# ep2c5_02.net
KiCad netlist of a schematic drawn in EAGLE
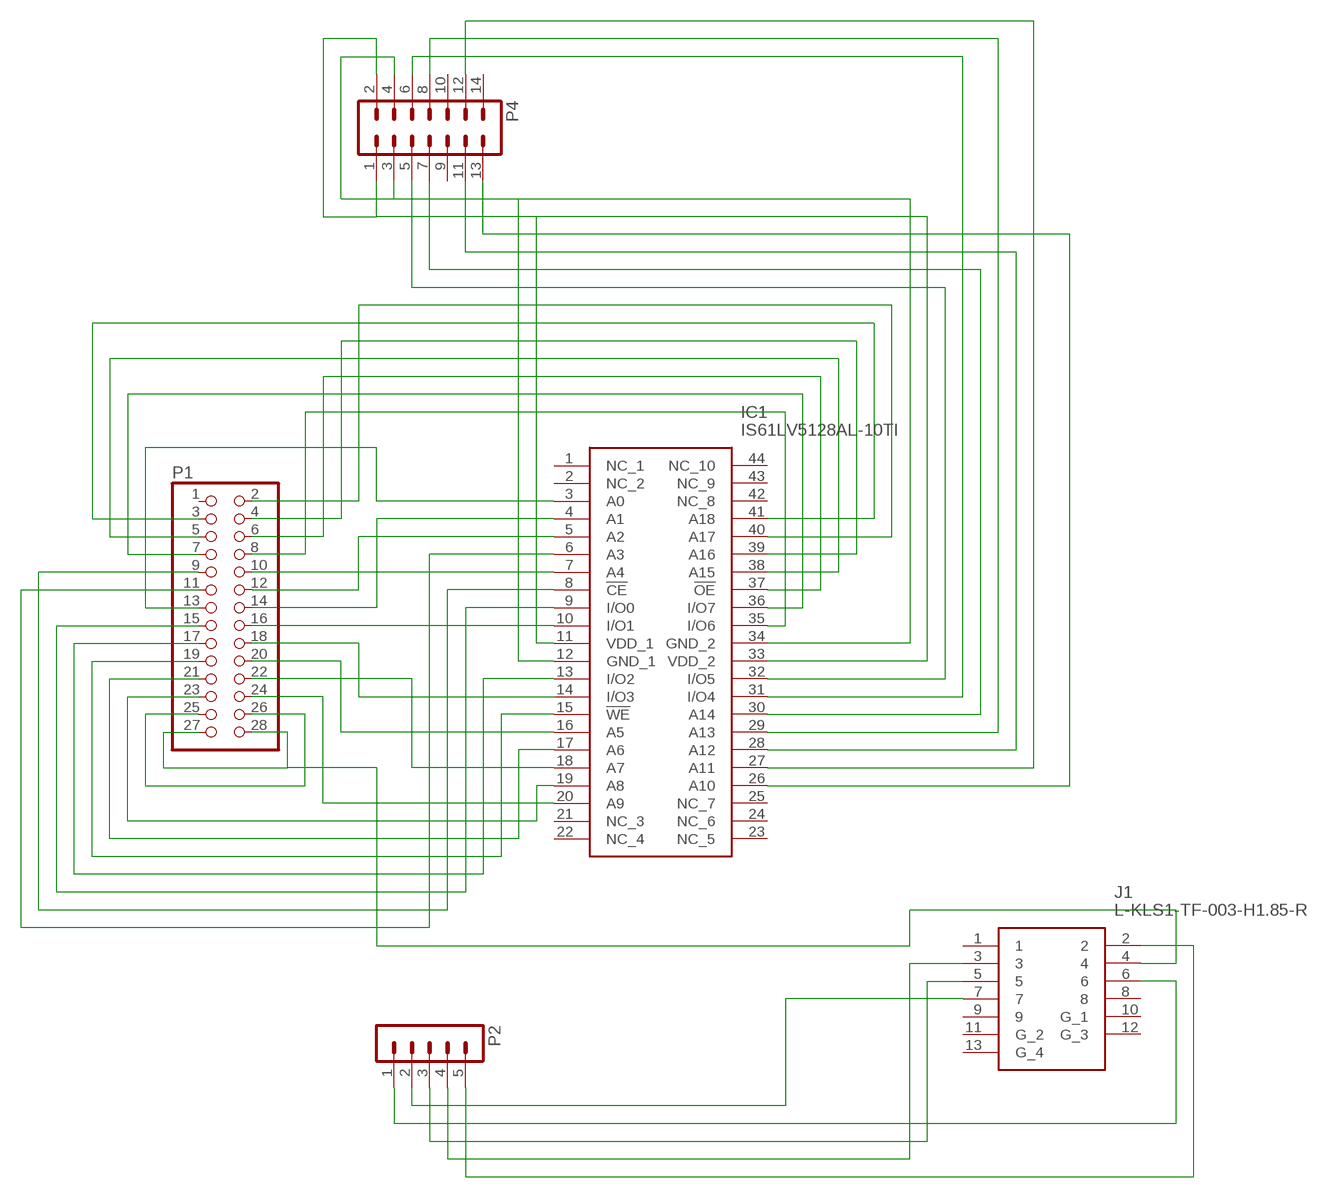
[diagram p0: schematic, sheet 1]

(export (version "E")
  (design (tool "Eeschema 10.0.6"))
  (components
    (comp (ref "IC1")
      (value "IS61LV5128AL-10TI")
      (footprint "eagle-import:SOP80P1176X120-44N")
      (fields (field (name "MOUSER_PART_NUMBER") "870IS61LV5128AL10TI"))
      (libsource (lib "eagle-import") (part "IS61LV5128AL-10TI"))
    )
    (comp (ref "J1")
      (value "L-KLS1-TF-003-H1.85-R")
      (footprint "eagle-import:L-KLS1-TF-003-H1.85-R")
      (libsource (lib "eagle-import") (part "L-KLS1-TF-003-H1.85-R"))
    )
    (comp (ref "P1")
      (value "PINHD-2X14")
      (footprint "eagle-import:2X14")
      (libsource (lib "eagle-import") (part "PINHD-2X14"))
    )
    (comp (ref "P2")
      (value "MA05-1")
      (footprint "eagle-import:MA05-1")
      (libsource (lib "eagle-import") (part "MA05-1"))
    )
    (comp (ref "P4")
      (value "MA07-2")
      (footprint "eagle-import:MA07-2")
      (libsource (lib "eagle-import") (part "MA07-2"))
    )
  )
  (nets
    (net (code "1") (name "Net-(IC1-A0)") (class "Default")
      (node (ref "IC1") (pin "3") (pinfunction "A0_3") (pintype "bidirectional"))
      (node (ref "P1") (pin "13") (pinfunction "13_13") (pintype "passive"))
    )
    (net (code "2") (name "Net-(IC1-A1)") (class "Default")
      (node (ref "IC1") (pin "4") (pinfunction "A1_4") (pintype "bidirectional"))
      (node (ref "P1") (pin "14") (pinfunction "14_14") (pintype "passive"))
    )
    (net (code "3") (name "Net-(IC1-A2)") (class "Default")
      (node (ref "IC1") (pin "5") (pinfunction "A2_5") (pintype "bidirectional"))
      (node (ref "P1") (pin "12") (pinfunction "12_12") (pintype "passive"))
    )
    (net (code "4") (name "Net-(IC1-A3)") (class "Default")
      (node (ref "IC1") (pin "6") (pinfunction "A3_6") (pintype "bidirectional"))
      (node (ref "P1") (pin "11") (pinfunction "11_11") (pintype "passive"))
    )
    (net (code "5") (name "Net-(IC1-A4)") (class "Default")
      (node (ref "IC1") (pin "7") (pinfunction "A4_7") (pintype "bidirectional"))
      (node (ref "P1") (pin "10") (pinfunction "10_10") (pintype "passive"))
    )
    (net (code "6") (name "Net-(IC1-A5)") (class "Default")
      (node (ref "IC1") (pin "16") (pinfunction "A5_16") (pintype "bidirectional"))
      (node (ref "P1") (pin "20") (pinfunction "20_20") (pintype "passive"))
    )
    (net (code "7") (name "Net-(IC1-A6)") (class "Default")
      (node (ref "IC1") (pin "17") (pinfunction "A6_17") (pintype "bidirectional"))
      (node (ref "P1") (pin "21") (pinfunction "21_21") (pintype "passive"))
    )
    (net (code "8") (name "Net-(IC1-A7)") (class "Default")
      (node (ref "IC1") (pin "18") (pinfunction "A7_18") (pintype "bidirectional"))
      (node (ref "P1") (pin "22") (pinfunction "22_22") (pintype "passive"))
    )
    (net (code "9") (name "Net-(IC1-A8)") (class "Default")
      (node (ref "IC1") (pin "19") (pinfunction "A8_19") (pintype "bidirectional"))
      (node (ref "P1") (pin "23") (pinfunction "23_23") (pintype "passive"))
    )
    (net (code "10") (name "Net-(IC1-A9)") (class "Default")
      (node (ref "IC1") (pin "20") (pinfunction "A9_20") (pintype "bidirectional"))
      (node (ref "P1") (pin "24") (pinfunction "24_24") (pintype "passive"))
    )
    (net (code "11") (name "Net-(IC1-A10)") (class "Default")
      (node (ref "IC1") (pin "26") (pinfunction "A10_26") (pintype "bidirectional"))
      (node (ref "P4") (pin "13") (pinfunction "13_13") (pintype "passive"))
    )
    (net (code "12") (name "Net-(IC1-A11)") (class "Default")
      (node (ref "IC1") (pin "27") (pinfunction "A11_27") (pintype "bidirectional"))
      (node (ref "P4") (pin "12") (pinfunction "12_12") (pintype "passive"))
    )
    (net (code "13") (name "Net-(IC1-A12)") (class "Default")
      (node (ref "IC1") (pin "28") (pinfunction "A12_28") (pintype "bidirectional"))
      (node (ref "P4") (pin "11") (pinfunction "11_11") (pintype "passive"))
    )
    (net (code "14") (name "Net-(IC1-A13)") (class "Default")
      (node (ref "IC1") (pin "29") (pinfunction "A13_29") (pintype "bidirectional"))
      (node (ref "P4") (pin "8") (pinfunction "8_8") (pintype "passive"))
    )
    (net (code "15") (name "Net-(IC1-A14)") (class "Default")
      (node (ref "IC1") (pin "30") (pinfunction "A14_30") (pintype "bidirectional"))
      (node (ref "P4") (pin "7") (pinfunction "7_7") (pintype "passive"))
    )
    (net (code "16") (name "Net-(IC1-A15)") (class "Default")
      (node (ref "IC1") (pin "38") (pinfunction "A15_38") (pintype "bidirectional"))
      (node (ref "P1") (pin "5") (pinfunction "5_5") (pintype "passive"))
    )
    (net (code "17") (name "Net-(IC1-A16)") (class "Default")
      (node (ref "IC1") (pin "39") (pinfunction "A16_39") (pintype "bidirectional"))
      (node (ref "P1") (pin "4") (pinfunction "4_4") (pintype "passive"))
    )
    (net (code "18") (name "Net-(IC1-A17)") (class "Default")
      (node (ref "IC1") (pin "40") (pinfunction "A17_40") (pintype "bidirectional"))
      (node (ref "P1") (pin "2") (pinfunction "2_2") (pintype "passive"))
    )
    (net (code "19") (name "Net-(IC1-A18)") (class "Default")
      (node (ref "IC1") (pin "41") (pinfunction "A18_41") (pintype "bidirectional"))
      (node (ref "P1") (pin "3") (pinfunction "3_3") (pintype "passive"))
    )
    (net (code "20") (name "Net-(IC1-GND_1)") (class "Default")
      (node (ref "IC1") (pin "12") (pinfunction "GND_1_12") (pintype "bidirectional"))
      (node (ref "IC1") (pin "34") (pinfunction "GND_2_34") (pintype "bidirectional"))
      (node (ref "P4") (pin "3") (pinfunction "3_3") (pintype "passive"))
      (node (ref "P4") (pin "4") (pinfunction "4_4") (pintype "passive"))
    )
    (net (code "21") (name "Net-(IC1-I{slash}O0)") (class "Default")
      (node (ref "IC1") (pin "9") (pinfunction "I/O0_9") (pintype "bidirectional"))
      (node (ref "P1") (pin "15") (pinfunction "15_15") (pintype "passive"))
    )
    (net (code "22") (name "Net-(IC1-I{slash}O1)") (class "Default")
      (node (ref "IC1") (pin "10") (pinfunction "I/O1_10") (pintype "bidirectional"))
      (node (ref "P1") (pin "16") (pinfunction "16_16") (pintype "passive"))
    )
    (net (code "23") (name "Net-(IC1-I{slash}O2)") (class "Default")
      (node (ref "IC1") (pin "13") (pinfunction "I/O2_13") (pintype "bidirectional"))
      (node (ref "P1") (pin "17") (pinfunction "17_17") (pintype "passive"))
    )
    (net (code "24") (name "Net-(IC1-I{slash}O3)") (class "Default")
      (node (ref "IC1") (pin "14") (pinfunction "I/O3_14") (pintype "bidirectional"))
      (node (ref "P1") (pin "18") (pinfunction "18_18") (pintype "passive"))
    )
    (net (code "25") (name "Net-(IC1-I{slash}O4)") (class "Default")
      (node (ref "IC1") (pin "31") (pinfunction "I/O4_31") (pintype "bidirectional"))
      (node (ref "P4") (pin "6") (pinfunction "6_6") (pintype "passive"))
    )
    (net (code "26") (name "Net-(IC1-I{slash}O5)") (class "Default")
      (node (ref "IC1") (pin "32") (pinfunction "I/O5_32") (pintype "bidirectional"))
      (node (ref "P4") (pin "5") (pinfunction "5_5") (pintype "passive"))
    )
    (net (code "27") (name "Net-(IC1-I{slash}O6)") (class "Default")
      (node (ref "IC1") (pin "35") (pinfunction "I/O6_35") (pintype "bidirectional"))
      (node (ref "P1") (pin "8") (pinfunction "8_8") (pintype "passive"))
    )
    (net (code "28") (name "Net-(IC1-I{slash}O7)") (class "Default")
      (node (ref "IC1") (pin "36") (pinfunction "I/O7_36") (pintype "bidirectional"))
      (node (ref "P1") (pin "7") (pinfunction "7_7") (pintype "passive"))
    )
    (net (code "29") (name "Net-(IC1-VDD_1)") (class "Default")
      (node (ref "IC1") (pin "11") (pinfunction "VDD_1_11") (pintype "bidirectional"))
      (node (ref "IC1") (pin "33") (pinfunction "VDD_2_33") (pintype "bidirectional"))
      (node (ref "P4") (pin "1") (pinfunction "1_1") (pintype "passive"))
      (node (ref "P4") (pin "2") (pinfunction "2_2") (pintype "passive"))
    )
    (net (code "30") (name "Net-(IC1-~{CE})") (class "Default")
      (node (ref "IC1") (pin "8") (pinfunction "~{CE}_8") (pintype "bidirectional"))
      (node (ref "P1") (pin "9") (pinfunction "9_9") (pintype "passive"))
    )
    (net (code "31") (name "Net-(IC1-~{OE})") (class "Default")
      (node (ref "IC1") (pin "37") (pinfunction "~{OE}_37") (pintype "bidirectional"))
      (node (ref "P1") (pin "6") (pinfunction "6_6") (pintype "passive"))
    )
    (net (code "32") (name "Net-(IC1-~{WE})") (class "Default")
      (node (ref "IC1") (pin "15") (pinfunction "~{WE}_15") (pintype "bidirectional"))
      (node (ref "P1") (pin "19") (pinfunction "19_19") (pintype "passive"))
    )
    (net (code "33") (name "Net-(J1-Pad2)") (class "Default")
      (node (ref "J1") (pin "2") (pinfunction "2_2") (pintype "bidirectional"))
      (node (ref "P2") (pin "5") (pinfunction "5_5") (pintype "passive"))
    )
    (net (code "34") (name "Net-(J1-Pad3)") (class "Default")
      (node (ref "J1") (pin "3") (pinfunction "3_3") (pintype "bidirectional"))
      (node (ref "P2") (pin "4") (pinfunction "4_4") (pintype "passive"))
    )
    (net (code "35") (name "Net-(J1-Pad4)") (class "Default")
      (node (ref "J1") (pin "4") (pinfunction "4_4") (pintype "bidirectional"))
      (node (ref "P1") (pin "27") (pinfunction "27_27") (pintype "passive"))
      (node (ref "P1") (pin "28") (pinfunction "28_28") (pintype "passive"))
    )
    (net (code "36") (name "Net-(J1-Pad5)") (class "Default")
      (node (ref "J1") (pin "5") (pinfunction "5_5") (pintype "bidirectional"))
      (node (ref "P2") (pin "3") (pinfunction "3_3") (pintype "passive"))
    )
    (net (code "37") (name "Net-(J1-Pad6)") (class "Default")
      (node (ref "J1") (pin "6") (pinfunction "6_6") (pintype "bidirectional"))
      (node (ref "P2") (pin "1") (pinfunction "1_1") (pintype "passive"))
    )
    (net (code "38") (name "Net-(J1-Pad7)") (class "Default")
      (node (ref "J1") (pin "7") (pinfunction "7_7") (pintype "bidirectional"))
      (node (ref "P2") (pin "2") (pinfunction "2_2") (pintype "passive"))
    )
    (net (code "39") (name "Net-(P1-Pad25)") (class "Default")
      (node (ref "P1") (pin "25") (pinfunction "25_25") (pintype "passive"))
      (node (ref "P1") (pin "26") (pinfunction "26_26") (pintype "passive"))
    )
    (net (code "40") (name "unconnected-(IC1-NC_1-Pad1)") (class "Default")
      (node (ref "IC1") (pin "1") (pinfunction "NC_1_1") (pintype "bidirectional"))
    )
    (net (code "41") (name "unconnected-(IC1-NC_2-Pad2)") (class "Default")
      (node (ref "IC1") (pin "2") (pinfunction "NC_2_2") (pintype "bidirectional"))
    )
    (net (code "42") (name "unconnected-(IC1-NC_3-Pad21)") (class "Default")
      (node (ref "IC1") (pin "21") (pinfunction "NC_3_21") (pintype "bidirectional"))
    )
    (net (code "43") (name "unconnected-(IC1-NC_4-Pad22)") (class "Default")
      (node (ref "IC1") (pin "22") (pinfunction "NC_4_22") (pintype "bidirectional"))
    )
    (net (code "44") (name "unconnected-(IC1-NC_5-Pad23)") (class "Default")
      (node (ref "IC1") (pin "23") (pinfunction "NC_5_23") (pintype "bidirectional"))
    )
    (net (code "45") (name "unconnected-(IC1-NC_6-Pad24)") (class "Default")
      (node (ref "IC1") (pin "24") (pinfunction "NC_6_24") (pintype "bidirectional"))
    )
    (net (code "46") (name "unconnected-(IC1-NC_7-Pad25)") (class "Default")
      (node (ref "IC1") (pin "25") (pinfunction "NC_7_25") (pintype "bidirectional"))
    )
    (net (code "47") (name "unconnected-(IC1-NC_8-Pad42)") (class "Default")
      (node (ref "IC1") (pin "42") (pinfunction "NC_8_42") (pintype "bidirectional"))
    )
    (net (code "48") (name "unconnected-(IC1-NC_9-Pad43)") (class "Default")
      (node (ref "IC1") (pin "43") (pinfunction "NC_9_43") (pintype "bidirectional"))
    )
    (net (code "49") (name "unconnected-(IC1-NC_10-Pad44)") (class "Default")
      (node (ref "IC1") (pin "44") (pinfunction "NC_10_44") (pintype "bidirectional"))
    )
    (net (code "50") (name "unconnected-(J1-G_1-Pad10)") (class "Default")
      (node (ref "J1") (pin "10") (pinfunction "G_1_10") (pintype "bidirectional"))
    )
    (net (code "51") (name "unconnected-(J1-G_2-Pad11)") (class "Default")
      (node (ref "J1") (pin "11") (pinfunction "G_2_11") (pintype "bidirectional"))
    )
    (net (code "52") (name "unconnected-(J1-G_3-Pad12)") (class "Default")
      (node (ref "J1") (pin "12") (pinfunction "G_3_12") (pintype "bidirectional"))
    )
    (net (code "53") (name "unconnected-(J1-G_4-Pad13)") (class "Default")
      (node (ref "J1") (pin "13") (pinfunction "G_4_13") (pintype "bidirectional"))
    )
    (net (code "54") (name "unconnected-(J1-Pad1)") (class "Default")
      (node (ref "J1") (pin "1") (pinfunction "1_1") (pintype "bidirectional"))
    )
    (net (code "55") (name "unconnected-(J1-Pad8)") (class "Default")
      (node (ref "J1") (pin "8") (pinfunction "8_8") (pintype "bidirectional"))
    )
    (net (code "56") (name "unconnected-(J1-Pad9)") (class "Default")
      (node (ref "J1") (pin "9") (pinfunction "9_9") (pintype "bidirectional"))
    )
    (net (code "57") (name "unconnected-(P1-Pad1)") (class "Default")
      (node (ref "P1") (pin "1") (pinfunction "1_1") (pintype "passive"))
    )
    (net (code "58") (name "unconnected-(P4-Pad9)") (class "Default")
      (node (ref "P4") (pin "9") (pinfunction "9_9") (pintype "passive"))
    )
    (net (code "59") (name "unconnected-(P4-Pad10)") (class "Default")
      (node (ref "P4") (pin "10") (pinfunction "10_10") (pintype "passive"))
    )
    (net (code "60") (name "unconnected-(P4-Pad14)") (class "Default")
      (node (ref "P4") (pin "14") (pinfunction "14_14") (pintype "passive"))
    )
  )
)
